# Sheet1.net
KiCad netlist of a schematic drawn in Altium Designer
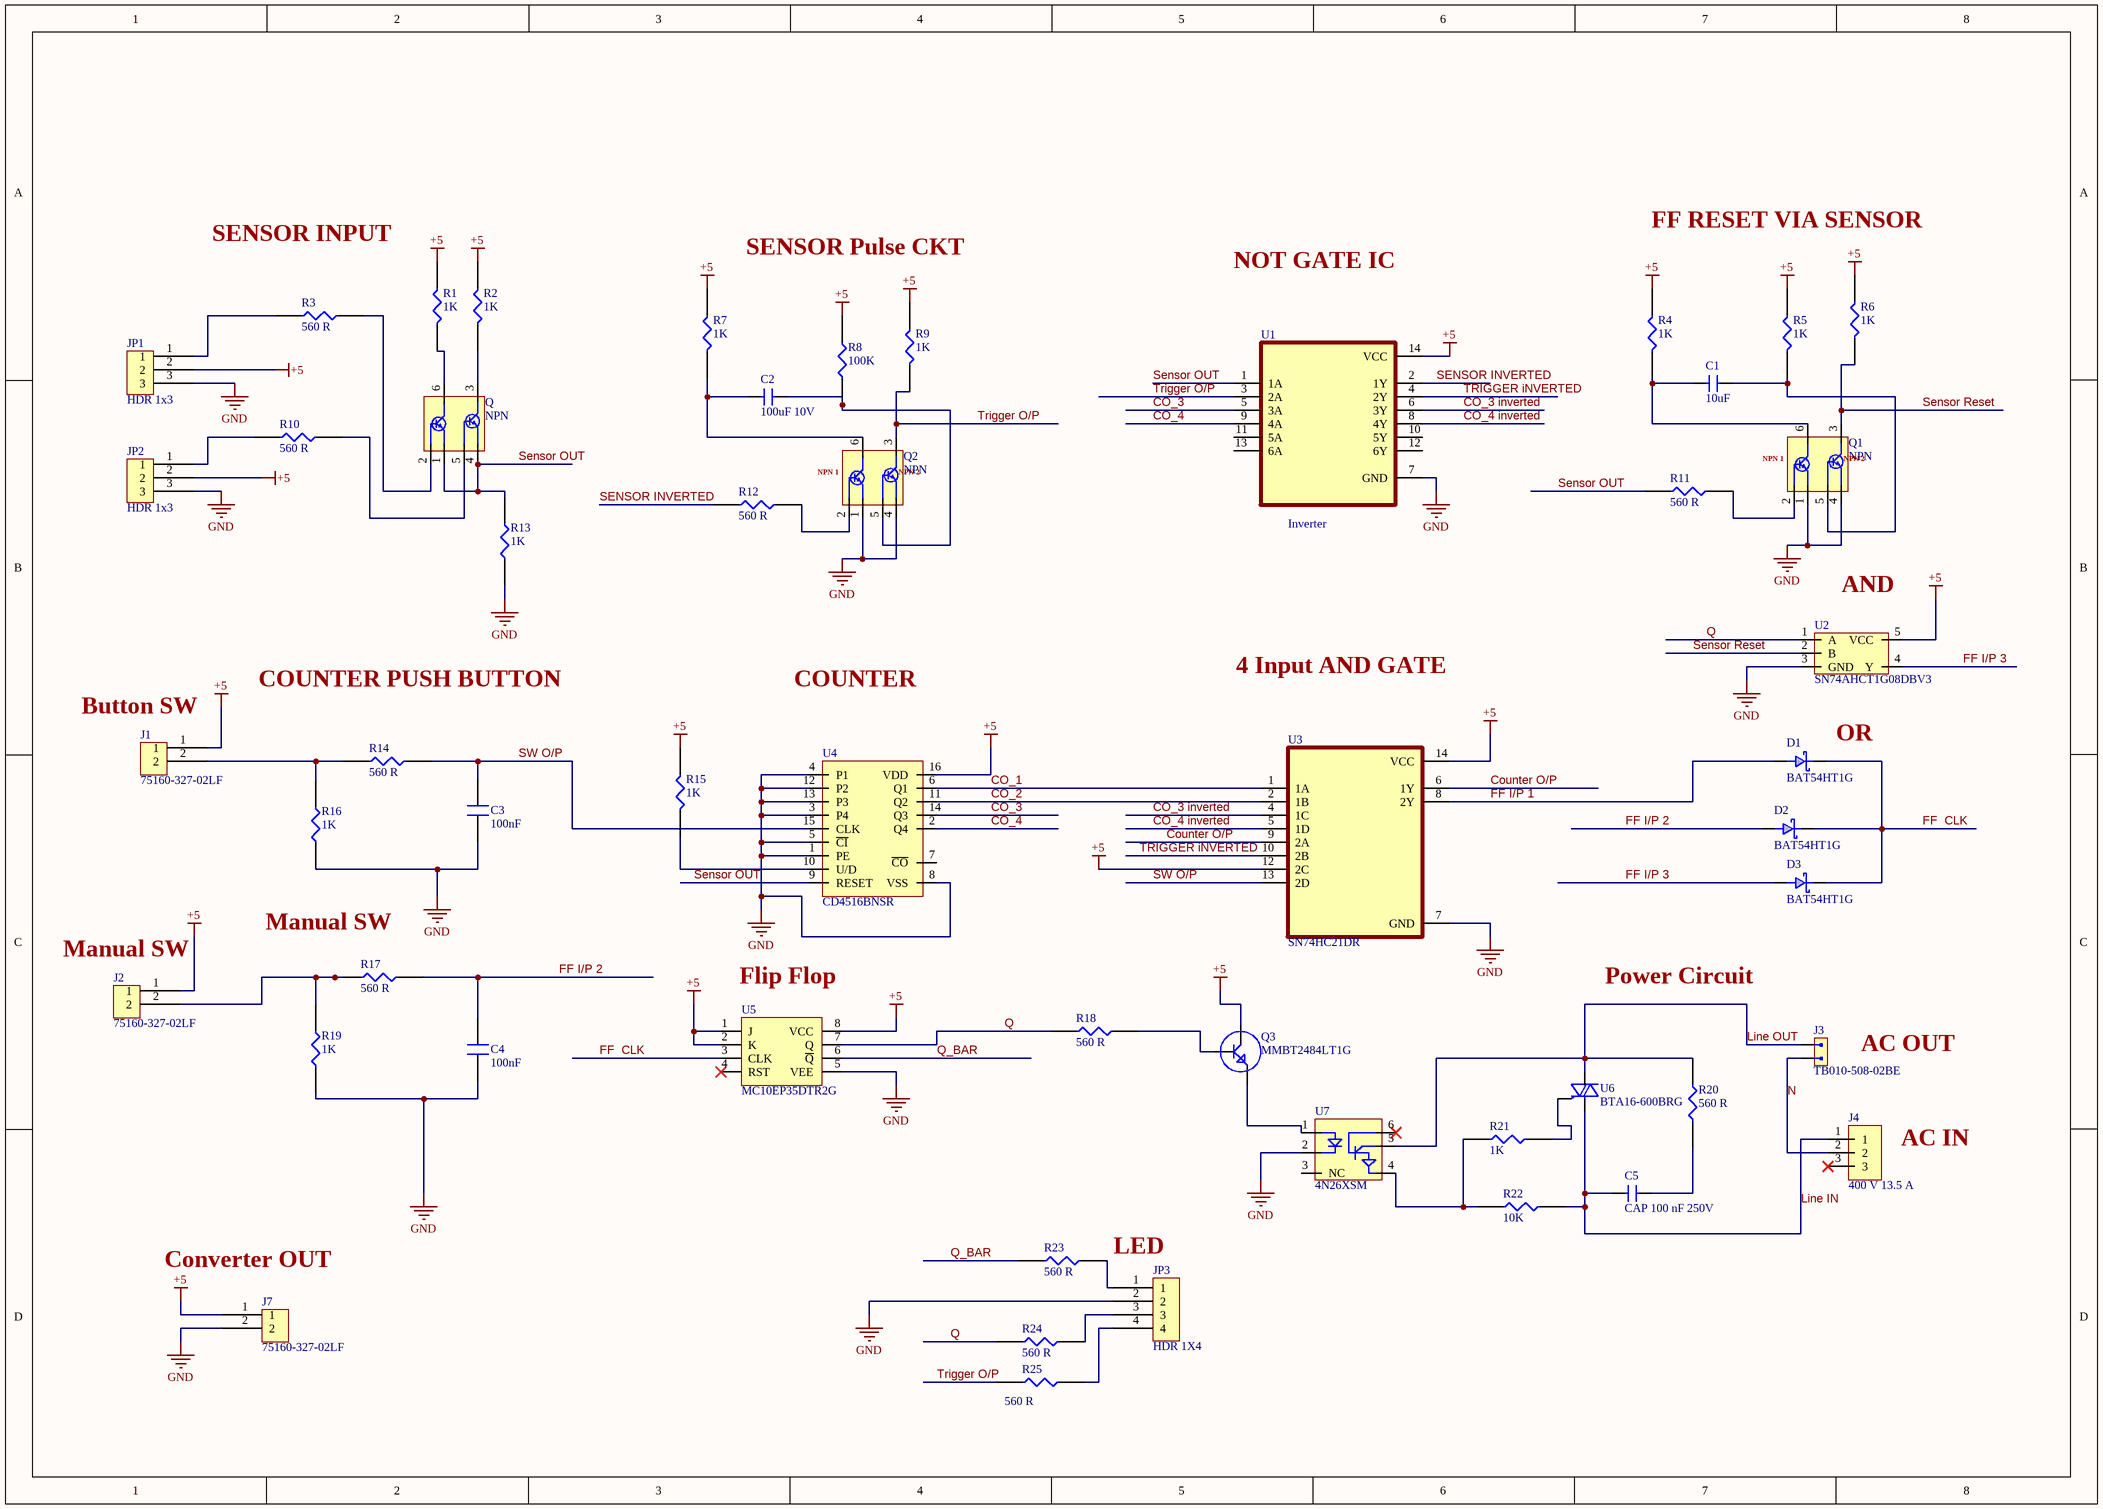
[diagram p0: Sheet1.SchDoc]

(export (version "E")
  (design (tool "Eeschema 10.0.6"))
  (components
    (comp (ref "C1")
      (value "10uF")
      (footprint "CAP_0805")
      (fields
        (field (name "MANUFACTURER") "TDK")
        (field (name "MANUFACTURER PART NUMBER") "C2012X5R1C106M125AC")
        (field (name "TOLERANCE") "20%")
      )
      (libsource (lib "Component Schematic Library V1") (part "CAP_10uF_0805"))
    )
    (comp (ref "C2")
      (value "100uF 10V")
      (footprint "CAP3216")
      (description "C Series 1206 100 uF 10 V ±20 % Tolerance JB SMT Multilayer Ceramic Capacitor")
      (fields
        (field (name "MANUFACTURER") "TDK")
        (field (name "MANUFACTURER PART NUMBER") "C3216JB1A107M160AC")
      )
      (libsource (lib "Component Schematic Library V1") (part "CAP 100 uF SMD Non Polar"))
    )
    (comp (ref "C3")
      (value "100nF")
      (footprint "CAP_0805")
      (description "C Series 0805 0.1 uF 50 V ±10 % Tolerance X7R SMT Multilayer Ceramic Capacitor")
      (fields
        (field (name "MANUFACTURER") "TDK")
        (field (name "MANUFACTURER PART NUMBER") "C2012X7R1H104K085AA")
      )
      (libsource (lib "Component Schematic Library V1") (part "CAP_100nF_0805"))
    )
    (comp (ref "C4")
      (value "100nF")
      (footprint "CAP_0805")
      (description "C Series 0805 0.1 uF 50 V ±10 % Tolerance X7R SMT Multilayer Ceramic Capacitor")
      (fields
        (field (name "MANUFACTURER") "TDK")
        (field (name "MANUFACTURER PART NUMBER") "C2012X7R1H104K085AA")
      )
      (libsource (lib "Component Schematic Library V1") (part "CAP_100nF_0805"))
    )
    (comp (ref "C5")
      (value "CAP 100 nF 250V")
      (footprint "CAP_0805")
      (description "C Series 0805 0.1 uF 250 V ±20 % Tolerance X7T SMT Multilayer Ceramic Capacitor")
      (libsource (lib "Component Schematic Library V1") (part "CAP 100 nF 250V"))
    )
    (comp (ref "D1")
      (value "BAT54HT1G")
      (footprint "SOD323")
      (description "VR=30V IF=200mA 10pF P=200mW")
      (fields (field (name "MANUFACTURER") "ON Semiconductor / Fairchild"))
      (libsource (lib "Component Schematic Library V1") (part "Shottky_Diode"))
    )
    (comp (ref "D2")
      (value "BAT54HT1G")
      (footprint "SOD323")
      (description "VR=30V IF=200mA 10pF P=200mW")
      (fields (field (name "MANUFACTURER") "ON Semiconductor / Fairchild"))
      (libsource (lib "Component Schematic Library V1") (part "Shottky_Diode"))
    )
    (comp (ref "D3")
      (value "BAT54HT1G")
      (footprint "SOD323")
      (description "VR=30V IF=200mA 10pF P=200mW")
      (fields (field (name "MANUFACTURER") "ON Semiconductor / Fairchild"))
      (libsource (lib "Component Schematic Library V1") (part "Shottky_Diode"))
    )
    (comp (ref "J1")
      (value "75160-327-02LF")
      (footprint "HDR 1x2")
      (description "Conn Unshrouded Header HDR 2 POS 2.54mm Solder ST Thru-Hole Poly Bag")
      (fields (field (name "MANUFACTURER") "Amphenol ICC / FCI"))
      (libsource (lib "") (part "MALE_HDR_1X2_1"))
    )
    (comp (ref "J2")
      (value "75160-327-02LF")
      (footprint "HDR 1x2")
      (description "Conn Unshrouded Header HDR 2 POS 2.54mm Solder ST Thru-Hole Poly Bag")
      (fields (field (name "MANUFACTURER") "Amphenol ICC / FCI"))
      (libsource (lib "") (part "MALE_HDR_1X2_1"))
    )
    (comp (ref "J3")
      (value "TB010-508-02BE")
      (footprint "CUI_TB010-508-02BE")
      (description "2~24 Poles, Screw Type, Horizontal, 5.08 Pitch, 26~12 (AWG), Terminal Block Connector")
      (fields (field (name "MANUFACTURER") "CUI Devices"))
      (libsource (lib "Component Schematic Library V1") (part "Screw terminal 2 pin"))
    )
    (comp (ref "J4")
      (value "400 V 13.5 A")
      (footprint "Screw 5mm 3 Terminal")
      (description "Phoenix Contact 5441540, BC-500X10- 3 BK PCB terminal blo")
      (fields
        (field (name "MANUFACTURER") "Phoenix Contact")
        (field (name "MANUFACTURER PART NUMBER") "5441540")
      )
      (libsource (lib "Component Schematic Library V1") (part "Screw Terminal HV 3 pins"))
    )
    (comp (ref "J7")
      (value "75160-327-02LF")
      (footprint "HDR 1x2")
      (description "Conn Unshrouded Header HDR 2 POS 2.54mm Solder ST Thru-Hole Poly Bag")
      (fields (field (name "MANUFACTURER") "Amphenol ICC / FCI"))
      (libsource (lib "Component Schematic Library V1") (part "MALE_HDR_1X2"))
    )
    (comp (ref "JP1")
      (value "HDR 1x3")
      (footprint "HDR 1x3")
      (description "Conn Unshrouded Header HDR 3 POS 2.54mm Solder ST Top Entry Thru-Hole BergStik® Bulk")
      (fields
        (field (name "MANUFACTURER") "Amphenol ICC / FCI")
        (field (name "MANUFACTURER PART NUMBER") "68797-403HLF")
      )
      (libsource (lib "Component Schematic Library V1") (part "Male_HDR_1X3_Unschrouded"))
    )
    (comp (ref "JP2")
      (value "HDR 1x3")
      (footprint "HDR 1x3")
      (description "Conn Unshrouded Header HDR 3 POS 2.54mm Solder ST Top Entry Thru-Hole BergStik® Bulk")
      (fields
        (field (name "MANUFACTURER") "Amphenol ICC / FCI")
        (field (name "MANUFACTURER PART NUMBER") "68797-403HLF")
      )
      (libsource (lib "Component Schematic Library V1") (part "Male_HDR_1X3_Unschrouded"))
    )
    (comp (ref "JP3")
      (value "HDR 1X4")
      (footprint "HDR 1X4")
      (description "Conn Unshrouded Header HDR 4 POS 2.54mm Solder ST Thru-Hole Bag")
      (fields
        (field (name "MANUFACTURER") "Amphenol ICC")
        (field (name "MANUFACTURER PART NUMBER") "68001-204HLF")
      )
      (libsource (lib "Component Schematic Library V1") (part "MALE_HDR_4X1_Unschrouded"))
    )
    (comp (ref "Q")
      (value "NPN")
      (footprint "SOT-363")
      (description "三极管 2NPN Vceo=40V Ic=200mA Pd=225mW")
      (fields
        (field (name "MANUFACTURER") "Pan Jit")
        (field (name "MANUFACTURER PART NUMBER") "MMDT3904_R1_00001")
      )
      (libsource (lib "Component Schematic Library V1") (part "NPN SMD 2 CKT"))
    )
    (comp (ref "Q1")
      (value "NPN")
      (footprint "SOT-363")
      (description "三极管 2NPN Vceo=40V Ic=200mA Pd=225mW")
      (fields
        (field (name "MANUFACTURER") "Pan Jit")
        (field (name "MANUFACTURER PART NUMBER") "MMDT3904_R1_00001")
      )
      (libsource (lib "Component Schematic Library V1") (part "NPN SMD 2 CKT"))
    )
    (comp (ref "Q2")
      (value "NPN")
      (footprint "SOT-363")
      (description "三极管 2NPN Vceo=40V Ic=200mA Pd=225mW")
      (fields
        (field (name "MANUFACTURER") "Pan Jit")
        (field (name "MANUFACTURER PART NUMBER") "MMDT3904_R1_00001")
      )
      (libsource (lib "Component Schematic Library V1") (part "NPN SMD 2 CKT"))
    )
    (comp (ref "Q3")
      (value "MMBT2484LT1G")
      (footprint "SOT23-3")
      (description "Transistor Bipolar (BJT) NPN 60V 100mA 225mW Surface Mount SOT-23-3")
      (fields (field (name "MANUFACTURER") "ON Semiconductor"))
      (libsource (lib "Component Schematic Library V1") (part "BJT SMD"))
    )
    (comp (ref "R1")
      (value "1K")
      (footprint "R_0805")
      (description "贴片电阻 1000Ω ± 1.00% 0.125W ± 100ppm/℃ 0805")
      (fields
        (field (name "MANUFACTURER") "Yageo")
        (field (name "MANUFACTURER PART NUMBER") "RC0805FR-071KL")
      )
      (libsource (lib "Component Schematic Library V1") (part "RES_1_K_0805"))
    )
    (comp (ref "R2")
      (value "1K")
      (footprint "R_0805")
      (description "贴片电阻 1000Ω ± 1.00% 0.125W ± 100ppm/℃ 0805")
      (fields
        (field (name "MANUFACTURER") "Yageo")
        (field (name "MANUFACTURER PART NUMBER") "RC0805FR-071KL")
      )
      (libsource (lib "Component Schematic Library V1") (part "RES_1_K_0805"))
    )
    (comp (ref "R3")
      (value "560 R")
      (footprint "R_0805")
      (description "贴片电阻 560Ω ± 1.00% 0.125W ± 100ppm/℃ 0805")
      (fields
        (field (name "MANUFACTURER") "Yageo")
        (field (name "MANUFACTURER PART NUMBER") "RC0805FR-07560RL")
      )
      (libsource (lib "Component Schematic Library V1") (part "RES_560_Ohm_0805"))
    )
    (comp (ref "R4")
      (value "1K")
      (footprint "R_0805")
      (description "贴片电阻 1000Ω ± 1.00% 0.125W ± 100ppm/℃ 0805")
      (fields
        (field (name "MANUFACTURER") "Yageo")
        (field (name "MANUFACTURER PART NUMBER") "RC0805FR-071KL")
      )
      (libsource (lib "Component Schematic Library V1") (part "RES_1_K_0805"))
    )
    (comp (ref "R5")
      (value "1K")
      (footprint "R_0805")
      (description "贴片电阻 1000Ω ± 1.00% 0.125W ± 100ppm/℃ 0805")
      (fields
        (field (name "MANUFACTURER") "Yageo")
        (field (name "MANUFACTURER PART NUMBER") "RC0805FR-071KL")
      )
      (libsource (lib "Component Schematic Library V1") (part "RES_1_K_0805"))
    )
    (comp (ref "R6")
      (value "1K")
      (footprint "R_0805")
      (description "贴片电阻 1000Ω ± 1.00% 0.125W ± 100ppm/℃ 0805")
      (fields
        (field (name "MANUFACTURER") "Yageo")
        (field (name "MANUFACTURER PART NUMBER") "RC0805FR-071KL")
      )
      (libsource (lib "Component Schematic Library V1") (part "RES_1_K_0805"))
    )
    (comp (ref "R7")
      (value "1K")
      (footprint "R_0805")
      (description "贴片电阻 1000Ω ± 1.00% 0.125W ± 100ppm/℃ 0805")
      (fields
        (field (name "MANUFACTURER") "Yageo")
        (field (name "MANUFACTURER PART NUMBER") "RC0805FR-071KL")
      )
      (libsource (lib "Component Schematic Library V1") (part "RES_1_K_0805"))
    )
    (comp (ref "R8")
      (value "100K")
      (footprint "R_0805")
      (description "贴片电阻 100000Ω ± 1.00% 0.125W ± 100ppm/℃ 0805")
      (fields
        (field (name "MANUFACTURER") "Yageo")
        (field (name "MANUFACTURER PART NUMBER") "RC0805FR-07100KL")
      )
      (libsource (lib "Component Schematic Library V1") (part "RES_100_K_0805"))
    )
    (comp (ref "R9")
      (value "1K")
      (footprint "R_0805")
      (description "贴片电阻 1000Ω ± 1.00% 0.125W ± 100ppm/℃ 0805")
      (fields
        (field (name "MANUFACTURER") "Yageo")
        (field (name "MANUFACTURER PART NUMBER") "RC0805FR-071KL")
      )
      (libsource (lib "Component Schematic Library V1") (part "RES_1_K_0805"))
    )
    (comp (ref "R10")
      (value "560 R")
      (footprint "R_0805")
      (description "贴片电阻 560Ω ± 1.00% 0.125W ± 100ppm/℃ 0805")
      (fields
        (field (name "MANUFACTURER") "Yageo")
        (field (name "MANUFACTURER PART NUMBER") "RC0805FR-07560RL")
      )
      (libsource (lib "Component Schematic Library V1") (part "RES_560_Ohm_0805"))
    )
    (comp (ref "R11")
      (value "560 R")
      (footprint "R_0805")
      (description "贴片电阻 560Ω ± 1.00% 0.125W ± 100ppm/℃ 0805")
      (fields
        (field (name "MANUFACTURER") "Yageo")
        (field (name "MANUFACTURER PART NUMBER") "RC0805FR-07560RL")
      )
      (libsource (lib "Component Schematic Library V1") (part "RES_560_Ohm_0805"))
    )
    (comp (ref "R12")
      (value "560 R")
      (footprint "R_0805")
      (description "贴片电阻 560Ω ± 1.00% 0.125W ± 100ppm/℃ 0805")
      (fields
        (field (name "MANUFACTURER") "Yageo")
        (field (name "MANUFACTURER PART NUMBER") "RC0805FR-07560RL")
      )
      (libsource (lib "Component Schematic Library V1") (part "RES_560_Ohm_0805"))
    )
    (comp (ref "R13")
      (value "1K")
      (footprint "R_0805")
      (description "贴片电阻 1000Ω ± 1.00% 0.125W ± 100ppm/℃ 0805")
      (fields
        (field (name "MANUFACTURER") "Yageo")
        (field (name "MANUFACTURER PART NUMBER") "RC0805FR-071KL")
      )
      (libsource (lib "Component Schematic Library V1") (part "RES_1_K_0805"))
    )
    (comp (ref "R14")
      (value "560 R")
      (footprint "R_0805")
      (description "贴片电阻 560Ω ± 1.00% 0.125W ± 100ppm/℃ 0805")
      (fields
        (field (name "MANUFACTURER") "Yageo")
        (field (name "MANUFACTURER PART NUMBER") "RC0805FR-07560RL")
      )
      (libsource (lib "Component Schematic Library V1") (part "RES_560_Ohm_0805"))
    )
    (comp (ref "R15")
      (value "1K")
      (footprint "R_0805")
      (description "贴片电阻 1000Ω ± 1.00% 0.125W ± 100ppm/℃ 0805")
      (fields
        (field (name "MANUFACTURER") "Yageo")
        (field (name "MANUFACTURER PART NUMBER") "RC0805FR-071KL")
      )
      (libsource (lib "Component Schematic Library V1") (part "RES_1_K_0805"))
    )
    (comp (ref "R16")
      (value "1K")
      (footprint "R_0805")
      (description "贴片电阻 1000Ω ± 1.00% 0.125W ± 100ppm/℃ 0805")
      (fields
        (field (name "MANUFACTURER") "Yageo")
        (field (name "MANUFACTURER PART NUMBER") "RC0805FR-071KL")
      )
      (libsource (lib "Component Schematic Library V1") (part "RES_1_K_0805"))
    )
    (comp (ref "R17")
      (value "560 R")
      (footprint "R_0805")
      (description "贴片电阻 560Ω ± 1.00% 0.125W ± 100ppm/℃ 0805")
      (fields
        (field (name "MANUFACTURER") "Yageo")
        (field (name "MANUFACTURER PART NUMBER") "RC0805FR-07560RL")
      )
      (libsource (lib "Component Schematic Library V1") (part "RES_560_Ohm_0805"))
    )
    (comp (ref "R18")
      (value "560 R")
      (footprint "R_0805")
      (description "贴片电阻 560Ω ± 1.00% 0.125W ± 100ppm/℃ 0805")
      (fields
        (field (name "MANUFACTURER") "Yageo")
        (field (name "MANUFACTURER PART NUMBER") "RC0805FR-07560RL")
      )
      (libsource (lib "Component Schematic Library V1") (part "RES_560_Ohm_0805"))
    )
    (comp (ref "R19")
      (value "1K")
      (footprint "R_0805")
      (description "贴片电阻 1000Ω ± 1.00% 0.125W ± 100ppm/℃ 0805")
      (fields
        (field (name "MANUFACTURER") "Yageo")
        (field (name "MANUFACTURER PART NUMBER") "RC0805FR-071KL")
      )
      (libsource (lib "Component Schematic Library V1") (part "RES_1_K_0805"))
    )
    (comp (ref "R20")
      (value "560 R")
      (footprint "R_0805")
      (description "贴片电阻 560Ω ± 1.00% 0.125W ± 100ppm/℃ 0805")
      (fields
        (field (name "MANUFACTURER") "Yageo")
        (field (name "MANUFACTURER PART NUMBER") "RC0805FR-07560RL")
      )
      (libsource (lib "Component Schematic Library V1") (part "RES_560_Ohm_0805"))
    )
    (comp (ref "R21")
      (value "1K")
      (footprint "R_0805")
      (description "贴片电阻 1000Ω ± 1.00% 0.125W ± 100ppm/℃ 0805")
      (fields
        (field (name "MANUFACTURER") "Yageo")
        (field (name "MANUFACTURER PART NUMBER") "RC0805FR-071KL")
      )
      (libsource (lib "Component Schematic Library V1") (part "RES_1_K_0805"))
    )
    (comp (ref "R22")
      (value "10K")
      (footprint "R_0805")
      (description "贴片电阻 10000Ω ± 1.00% 0.125W ± 100ppm/℃ 0805")
      (fields
        (field (name "MANUFACTURER") "Yageo")
        (field (name "MANUFACTURER PART NUMBER") "RC0805FR-0710KL")
      )
      (libsource (lib "Component Schematic Library V1") (part "RES_10_K_0805"))
    )
    (comp (ref "R23")
      (value "560 R")
      (footprint "R_0805")
      (description "贴片电阻 560Ω ± 1.00% 0.125W ± 100ppm/℃ 0805")
      (fields
        (field (name "MANUFACTURER") "Yageo")
        (field (name "MANUFACTURER PART NUMBER") "RC0805FR-07560RL")
      )
      (libsource (lib "Component Schematic Library V1") (part "RES_560_Ohm_0805"))
    )
    (comp (ref "R24")
      (value "560 R")
      (footprint "R_0805")
      (description "贴片电阻 560Ω ± 1.00% 0.125W ± 100ppm/℃ 0805")
      (fields
        (field (name "MANUFACTURER") "Yageo")
        (field (name "MANUFACTURER PART NUMBER") "RC0805FR-07560RL")
      )
      (libsource (lib "Component Schematic Library V1") (part "RES_560_Ohm_0805"))
    )
    (comp (ref "R25")
      (value "560 R")
      (footprint "R_0805")
      (description "贴片电阻 560Ω ± 1.00% 0.125W ± 100ppm/℃ 0805")
      (fields
        (field (name "MANUFACTURER") "Yageo")
        (field (name "MANUFACTURER PART NUMBER") "RC0805FR-07560RL")
      )
      (libsource (lib "Component Schematic Library V1") (part "RES_560_Ohm_0805"))
    )
    (comp (ref "U1")
      (value "Inverter")
      (footprint "14-TSSOP")
      (description "6-ch, 4.5-V to 5.5-V inverters with Schmitt-Trigger inputs 14-TSSOP -40 to 85")
      (fields
        (field (name "MANUFACTURER") "Texas Instruments")
        (field (name "MANUFACTURER PART NUMBER") "SN74ACT14PWR")
      )
      (libsource (lib "Component Schematic Library V1") (part "NOT GATE 7 Channel"))
    )
    (comp (ref "U2")
      (value "SN74AHCT1G08DBV3")
      (footprint "SOT-23-5")
      (description "Single 2-input, 4.5-V to 5.5-V AND gate with TTL-compatible CMOS inputs 5-SOT-23 -40 to 125")
      (fields (field (name "MANUFACTURER") "Texas Instruments"))
      (libsource (lib "Component Schematic Library V1") (part "AND 2 INP 1 CKT"))
    )
    (comp (ref "U3")
      (value "SN74HC21DR")
      (footprint "SOIC 14")
      (description "AND Gate IC 2 Channel  14-SOIC")
      (fields (field (name "MANUFACTURER") "Texas Instruments"))
      (libsource (lib "Component Schematic Library V1") (part "AND 4 inp 2 ch SMD"))
    )
    (comp (ref "U4")
      (value "CD4516BNSR")
      (footprint "SOIC 16")
      (description "CMOS Presettable Binary Up/Down Counter 16-SO -55 to 125")
      (fields (field (name "MANUFACTURER") "Texas Instruments"))
      (libsource (lib "Component Schematic Library V1") (part "COUNTER CD4516BNSR"))
    )
    (comp (ref "U5")
      (value "MC10EP35DTR2G")
      (footprint "8-TSSOP")
      (description "Flip Flop JK-Type Pos-Edge 1-Element 8-Pin TSSOP T/R")
      (fields (field (name "MANUFACTURER") "ON Semiconductor"))
      (libsource (lib "Component Schematic Library V1") (part "JK Flipflop"))
    )
    (comp (ref "U6")
      (value "BTA16-600BRG")
      (footprint "BAT16")
      (description "TRIAC Standard 600V 16A Through Hole TO-220AB")
      (libsource (lib "Component Schematic Library V1") (part "Triac"))
    )
    (comp (ref "U7")
      (value "4N26XSM")
      (footprint "SMD 6")
      (description "DC-IN 1-CH Transistor With Base DC-OUT 6-Pin PDIP SMD")
      (fields (field (name "MANUFACTURER") "Isocom"))
      (libsource (lib "Component Schematic Library V1") (part "4N26XSM"))
    )
  )
  (nets
    (net (code "1") (name "+5") (class "Default")
      (node (ref "J1") (pin "1") (pinfunction "1_1") (pintype "passive"))
      (node (ref "J2") (pin "1") (pinfunction "1_1") (pintype "passive"))
      (node (ref "J7") (pin "1") (pinfunction "1_1") (pintype "passive"))
      (node (ref "JP1") (pin "2") (pinfunction "2_2") (pintype "passive"))
      (node (ref "JP2") (pin "2") (pinfunction "2_2") (pintype "passive"))
      (node (ref "Q3") (pin "3") (pinfunction "3_3") (pintype "passive"))
      (node (ref "R1") (pin "2") (pinfunction "3_2") (pintype "passive"))
      (node (ref "R15") (pin "2") (pinfunction "3_2") (pintype "passive"))
      (node (ref "R2") (pin "2") (pinfunction "3_2") (pintype "passive"))
      (node (ref "R4") (pin "2") (pinfunction "3_2") (pintype "passive"))
      (node (ref "R5") (pin "2") (pinfunction "3_2") (pintype "passive"))
      (node (ref "R6") (pin "2") (pinfunction "3_2") (pintype "passive"))
      (node (ref "R7") (pin "2") (pinfunction "3_2") (pintype "passive"))
      (node (ref "R8") (pin "2") (pinfunction "3_2") (pintype "passive"))
      (node (ref "R9") (pin "2") (pinfunction "3_2") (pintype "passive"))
      (node (ref "U1") (pin "14") (pinfunction "VCC_14") (pintype "passive"))
      (node (ref "U2") (pin "5") (pinfunction "VCC_5") (pintype "passive"))
      (node (ref "U3") (pin "12") (pinfunction "2C_12") (pintype "passive"))
      (node (ref "U3") (pin "14") (pinfunction "VCC_14") (pintype "passive"))
      (node (ref "U4") (pin "16") (pinfunction "VDD_16") (pintype "passive"))
      (node (ref "U5") (pin "1") (pinfunction "J_1") (pintype "passive"))
      (node (ref "U5") (pin "2") (pinfunction "K_2") (pintype "passive"))
      (node (ref "U5") (pin "8") (pinfunction "VCC_8") (pintype "passive"))
    )
    (net (code "2") (name "/CO_1") (class "Default")
      (node (ref "U3") (pin "1") (pinfunction "1A_1") (pintype "passive"))
      (node (ref "U4") (pin "6") (pinfunction "Q1_6") (pintype "passive"))
    )
    (net (code "3") (name "/CO_2") (class "Default")
      (node (ref "U3") (pin "2") (pinfunction "1B_2") (pintype "passive"))
      (node (ref "U4") (pin "11") (pinfunction "Q2_11") (pintype "passive"))
    )
    (net (code "4") (name "/CO_3") (class "Default")
      (node (ref "U1") (pin "5") (pinfunction "3A_5") (pintype "passive"))
      (node (ref "U4") (pin "14") (pinfunction "Q3_14") (pintype "passive"))
    )
    (net (code "5") (name "/CO_3 inverted") (class "Default")
      (node (ref "U1") (pin "6") (pinfunction "3Y_6") (pintype "passive"))
      (node (ref "U3") (pin "4") (pinfunction "1C_4") (pintype "passive"))
    )
    (net (code "6") (name "/CO_4") (class "Default")
      (node (ref "U1") (pin "9") (pinfunction "4A_9") (pintype "passive"))
      (node (ref "U4") (pin "2") (pinfunction "Q4_2") (pintype "passive"))
    )
    (net (code "7") (name "/CO_4 inverted") (class "Default")
      (node (ref "U1") (pin "8") (pinfunction "4Y_8") (pintype "passive"))
      (node (ref "U3") (pin "5") (pinfunction "1D_5") (pintype "passive"))
    )
    (net (code "8") (name "/Counter O{slash}P") (class "Default")
      (node (ref "U3") (pin "6") (pinfunction "1Y_6") (pintype "passive"))
      (node (ref "U3") (pin "9") (pinfunction "2A_9") (pintype "passive"))
    )
    (net (code "9") (name "/FF  CLK") (class "Default")
      (node (ref "D1") (pin "1") (pinfunction "Cathode_1") (pintype "passive"))
      (node (ref "D2") (pin "1") (pinfunction "Cathode_1") (pintype "passive"))
      (node (ref "D3") (pin "1") (pinfunction "Cathode_1") (pintype "passive"))
      (node (ref "U5") (pin "3") (pinfunction "CLK_3") (pintype "passive"))
    )
    (net (code "10") (name "/FF I{slash}P 1") (class "Default")
      (node (ref "D1") (pin "2") (pinfunction "Anode_2") (pintype "passive"))
      (node (ref "U3") (pin "8") (pinfunction "2Y_8") (pintype "passive"))
    )
    (net (code "11") (name "/FF I{slash}P 2") (class "Default")
      (node (ref "C4") (pin "1") (pinfunction "1_1") (pintype "passive"))
      (node (ref "D2") (pin "2") (pinfunction "Anode_2") (pintype "passive"))
      (node (ref "R17") (pin "2") (pinfunction "3_2") (pintype "passive"))
    )
    (net (code "12") (name "/FF I{slash}P 3") (class "Default")
      (node (ref "D3") (pin "2") (pinfunction "Anode_2") (pintype "passive"))
      (node (ref "U2") (pin "4") (pinfunction "Y_4") (pintype "passive"))
    )
    (net (code "13") (name "/Line IN") (class "Default")
      (node (ref "C5") (pin "1") (pinfunction "1_1") (pintype "passive"))
      (node (ref "J4") (pin "1") (pinfunction "1_1") (pintype "passive"))
      (node (ref "R22") (pin "2") (pinfunction "3_2") (pintype "passive"))
      (node (ref "U6") (pin "1") (pinfunction "A1_1") (pintype "passive"))
    )
    (net (code "14") (name "/Line OUT") (class "Default")
      (node (ref "J3") (pin "1") (pinfunction "1_1") (pintype "passive"))
      (node (ref "R20") (pin "2") (pinfunction "3_2") (pintype "passive"))
      (node (ref "U6") (pin "2") (pinfunction "A2_2") (pintype "passive"))
      (node (ref "U7") (pin "5") (pinfunction "5_5") (pintype "passive"))
    )
    (net (code "15") (name "/N") (class "Default")
      (node (ref "J3") (pin "2") (pinfunction "2_2") (pintype "passive"))
      (node (ref "J4") (pin "2") (pinfunction "2_2") (pintype "passive"))
    )
    (net (code "16") (name "/Q") (class "Default")
      (node (ref "R18") (pin "1") (pinfunction "2_1") (pintype "passive"))
      (node (ref "R24") (pin "1") (pinfunction "2_1") (pintype "passive"))
      (node (ref "U2") (pin "1") (pinfunction "A_1") (pintype "passive"))
      (node (ref "U5") (pin "7") (pinfunction "Q_7") (pintype "passive"))
    )
    (net (code "17") (name "/Q_BAR") (class "Default")
      (node (ref "R23") (pin "1") (pinfunction "2_1") (pintype "passive"))
      (node (ref "U5") (pin "6") (pinfunction "~{Q}_6") (pintype "passive"))
    )
    (net (code "18") (name "/SENSOR INVERTED") (class "Default")
      (node (ref "R12") (pin "1") (pinfunction "2_1") (pintype "passive"))
      (node (ref "U1") (pin "2") (pinfunction "1Y_2") (pintype "passive"))
    )
    (net (code "19") (name "/SW O{slash}P") (class "Default")
      (node (ref "C3") (pin "1") (pinfunction "1_1") (pintype "passive"))
      (node (ref "R14") (pin "2") (pinfunction "3_2") (pintype "passive"))
      (node (ref "U3") (pin "13") (pinfunction "2D_13") (pintype "passive"))
      (node (ref "U4") (pin "15") (pinfunction "CLK_15") (pintype "passive"))
    )
    (net (code "20") (name "/Sensor OUT") (class "Default")
      (node (ref "Q") (pin "1") (pinfunction "E1_1") (pintype "passive"))
      (node (ref "Q") (pin "4") (pinfunction "E2_4") (pintype "passive"))
      (node (ref "R11") (pin "1") (pinfunction "2_1") (pintype "passive"))
      (node (ref "R13") (pin "2") (pinfunction "3_2") (pintype "passive"))
      (node (ref "U1") (pin "1") (pinfunction "1A_1") (pintype "passive"))
      (node (ref "U4") (pin "9") (pinfunction "RESET_9") (pintype "passive"))
    )
    (net (code "21") (name "/Sensor Reset") (class "Default")
      (node (ref "Q1") (pin "3") (pinfunction "C2_3") (pintype "passive"))
      (node (ref "R6") (pin "1") (pinfunction "2_1") (pintype "passive"))
      (node (ref "U2") (pin "2") (pinfunction "B_2") (pintype "passive"))
    )
    (net (code "22") (name "/TRIGGER iNVERTED") (class "Default")
      (node (ref "U1") (pin "4") (pinfunction "2Y_4") (pintype "passive"))
      (node (ref "U3") (pin "10") (pinfunction "2B_10") (pintype "passive"))
    )
    (net (code "23") (name "/Trigger O{slash}P") (class "Default")
      (node (ref "Q2") (pin "3") (pinfunction "C2_3") (pintype "passive"))
      (node (ref "R25") (pin "1") (pinfunction "2_1") (pintype "passive"))
      (node (ref "R9") (pin "1") (pinfunction "2_1") (pintype "passive"))
      (node (ref "U1") (pin "3") (pinfunction "2A_3") (pintype "passive"))
    )
    (net (code "24") (name "GND") (class "Default")
      (node (ref "C3") (pin "2") (pinfunction "2_2") (pintype "passive"))
      (node (ref "C4") (pin "2") (pinfunction "2_2") (pintype "passive"))
      (node (ref "J7") (pin "2") (pinfunction "2_2") (pintype "passive"))
      (node (ref "JP1") (pin "3") (pinfunction "3_3") (pintype "passive"))
      (node (ref "JP2") (pin "3") (pinfunction "3_3") (pintype "passive"))
      (node (ref "JP3") (pin "2") (pinfunction "2_2") (pintype "passive"))
      (node (ref "Q1") (pin "1") (pinfunction "E1_1") (pintype "passive"))
      (node (ref "Q1") (pin "4") (pinfunction "E2_4") (pintype "passive"))
      (node (ref "Q2") (pin "1") (pinfunction "E1_1") (pintype "passive"))
      (node (ref "Q2") (pin "4") (pinfunction "E2_4") (pintype "passive"))
      (node (ref "R13") (pin "1") (pinfunction "2_1") (pintype "passive"))
      (node (ref "R16") (pin "2") (pinfunction "3_2") (pintype "passive"))
      (node (ref "R19") (pin "2") (pinfunction "3_2") (pintype "passive"))
      (node (ref "U1") (pin "7") (pinfunction "GND_7") (pintype "passive"))
      (node (ref "U2") (pin "3") (pinfunction "GND_3") (pintype "passive"))
      (node (ref "U3") (pin "7") (pinfunction "GND_7") (pintype "passive"))
      (node (ref "U4") (pin "1") (pinfunction "PE_1") (pintype "passive"))
      (node (ref "U4") (pin "12") (pinfunction "P2_12") (pintype "passive"))
      (node (ref "U4") (pin "13") (pinfunction "P3_13") (pintype "passive"))
      (node (ref "U4") (pin "3") (pinfunction "P4_3") (pintype "passive"))
      (node (ref "U4") (pin "4") (pinfunction "P1_4") (pintype "passive"))
      (node (ref "U4") (pin "5") (pinfunction "~{CI}_5") (pintype "passive"))
      (node (ref "U4") (pin "8") (pinfunction "VSS_8") (pintype "passive"))
      (node (ref "U5") (pin "5") (pinfunction "VEE_5") (pintype "passive"))
      (node (ref "U7") (pin "2") (pinfunction "2_2") (pintype "passive"))
    )
    (net (code "25") (name "Net-(Q-B1)") (class "Default")
      (node (ref "Q") (pin "2") (pinfunction "B1_2") (pintype "passive"))
      (node (ref "R3") (pin "2") (pinfunction "3_2") (pintype "passive"))
    )
    (net (code "26") (name "Net-(Q-B2)") (class "Default")
      (node (ref "Q") (pin "5") (pinfunction "B2_5") (pintype "passive"))
      (node (ref "R10") (pin "2") (pinfunction "3_2") (pintype "passive"))
    )
    (net (code "27") (name "Net-(Q-C1)") (class "Default")
      (node (ref "Q") (pin "6") (pinfunction "C1_6") (pintype "passive"))
      (node (ref "R1") (pin "1") (pinfunction "2_1") (pintype "passive"))
    )
    (net (code "28") (name "Net-(Q-C2)") (class "Default")
      (node (ref "Q") (pin "3") (pinfunction "C2_3") (pintype "passive"))
      (node (ref "R2") (pin "1") (pinfunction "2_1") (pintype "passive"))
    )
    (net (code "29") (name "Net-(Q1-B1)") (class "Default")
      (node (ref "Q1") (pin "2") (pinfunction "B1_2") (pintype "passive"))
      (node (ref "R11") (pin "2") (pinfunction "3_2") (pintype "passive"))
    )
    (net (code "30") (name "Net-(Q1-B2)") (class "Default")
      (node (ref "C1") (pin "2") (pinfunction "2_2") (pintype "passive"))
      (node (ref "Q1") (pin "5") (pinfunction "B2_5") (pintype "passive"))
      (node (ref "R5") (pin "1") (pinfunction "2_1") (pintype "passive"))
    )
    (net (code "31") (name "Net-(Q1-C1)") (class "Default")
      (node (ref "C1") (pin "1") (pinfunction "1_1") (pintype "passive"))
      (node (ref "Q1") (pin "6") (pinfunction "C1_6") (pintype "passive"))
      (node (ref "R4") (pin "1") (pinfunction "2_1") (pintype "passive"))
    )
    (net (code "32") (name "Net-(Q2-B1)") (class "Default")
      (node (ref "Q2") (pin "2") (pinfunction "B1_2") (pintype "passive"))
      (node (ref "R12") (pin "2") (pinfunction "3_2") (pintype "passive"))
    )
    (net (code "33") (name "Net-(Q2-B2)") (class "Default")
      (node (ref "C2") (pin "2") (pinfunction "2_2") (pintype "passive"))
      (node (ref "Q2") (pin "5") (pinfunction "B2_5") (pintype "passive"))
      (node (ref "R8") (pin "1") (pinfunction "2_1") (pintype "passive"))
    )
    (net (code "34") (name "Net-(Q2-C1)") (class "Default")
      (node (ref "C2") (pin "1") (pinfunction "1_1") (pintype "passive"))
      (node (ref "Q2") (pin "6") (pinfunction "C1_6") (pintype "passive"))
      (node (ref "R7") (pin "1") (pinfunction "2_1") (pintype "passive"))
    )
    (net (code "35") (name "Net-(Q3-Pad2)") (class "Default")
      (node (ref "Q3") (pin "2") (pinfunction "2_2") (pintype "passive"))
      (node (ref "U7") (pin "1") (pinfunction "1_1") (pintype "passive"))
    )
    (net (code "36") (name "Net-(R3-2)") (class "Default")
      (node (ref "JP1") (pin "1") (pinfunction "1_1") (pintype "passive"))
      (node (ref "R3") (pin "1") (pinfunction "2_1") (pintype "passive"))
    )
    (net (code "37") (name "Net-(R10-2)") (class "Default")
      (node (ref "JP2") (pin "1") (pinfunction "1_1") (pintype "passive"))
      (node (ref "R10") (pin "1") (pinfunction "2_1") (pintype "passive"))
    )
    (net (code "38") (name "Net-(R14-2)") (class "Default")
      (node (ref "J1") (pin "2") (pinfunction "2_2") (pintype "passive"))
      (node (ref "R14") (pin "1") (pinfunction "2_1") (pintype "passive"))
      (node (ref "R16") (pin "1") (pinfunction "2_1") (pintype "passive"))
    )
    (net (code "39") (name "Net-(R15-2)") (class "Default")
      (node (ref "R15") (pin "1") (pinfunction "2_1") (pintype "passive"))
      (node (ref "U4") (pin "10") (pinfunction "U/D_10") (pintype "passive"))
    )
    (net (code "40") (name "Net-(R17-2)") (class "Default")
      (node (ref "J2") (pin "2") (pinfunction "2_2") (pintype "passive"))
      (node (ref "R17") (pin "1") (pinfunction "2_1") (pintype "passive"))
      (node (ref "R19") (pin "1") (pinfunction "2_1") (pintype "passive"))
    )
    (net (code "41") (name "Net-(R18-3)") (class "Default")
      (node (ref "Q3") (pin "1") (pinfunction "1_1") (pintype "passive"))
      (node (ref "R18") (pin "2") (pinfunction "3_2") (pintype "passive"))
    )
    (net (code "42") (name "Net-(R20-2)") (class "Default")
      (node (ref "C5") (pin "2") (pinfunction "2_2") (pintype "passive"))
      (node (ref "R20") (pin "1") (pinfunction "2_1") (pintype "passive"))
    )
    (net (code "43") (name "Net-(R21-2)") (class "Default")
      (node (ref "R21") (pin "1") (pinfunction "2_1") (pintype "passive"))
      (node (ref "R22") (pin "1") (pinfunction "2_1") (pintype "passive"))
      (node (ref "U7") (pin "4") (pinfunction "4_4") (pintype "passive"))
    )
    (net (code "44") (name "Net-(R21-3)") (class "Default")
      (node (ref "R21") (pin "2") (pinfunction "3_2") (pintype "passive"))
      (node (ref "U6") (pin "3") (pinfunction "G_3") (pintype "passive"))
    )
    (net (code "45") (name "Net-(R23-3)") (class "Default")
      (node (ref "JP3") (pin "1") (pinfunction "1_1") (pintype "passive"))
      (node (ref "R23") (pin "2") (pinfunction "3_2") (pintype "passive"))
    )
    (net (code "46") (name "Net-(R24-3)") (class "Default")
      (node (ref "JP3") (pin "3") (pinfunction "3_3") (pintype "passive"))
      (node (ref "R24") (pin "2") (pinfunction "3_2") (pintype "passive"))
    )
    (net (code "47") (name "Net-(R25-3)") (class "Default")
      (node (ref "JP3") (pin "4") (pinfunction "4_4") (pintype "passive"))
      (node (ref "R25") (pin "2") (pinfunction "3_2") (pintype "passive"))
    )
    (net (code "48") (name "unconnected-(J4-Pad3)") (class "Default")
      (node (ref "J4") (pin "3") (pinfunction "3_3") (pintype "passive+no_connect"))
    )
    (net (code "49") (name "unconnected-(U1-5A-Pad11)") (class "Default")
      (node (ref "U1") (pin "11") (pinfunction "5A_11") (pintype "passive"))
    )
    (net (code "50") (name "unconnected-(U1-5Y-Pad10)") (class "Default")
      (node (ref "U1") (pin "10") (pinfunction "5Y_10") (pintype "passive"))
    )
    (net (code "51") (name "unconnected-(U1-6A-Pad13)") (class "Default")
      (node (ref "U1") (pin "13") (pinfunction "6A_13") (pintype "passive"))
    )
    (net (code "52") (name "unconnected-(U1-6Y-Pad12)") (class "Default")
      (node (ref "U1") (pin "12") (pinfunction "6Y_12") (pintype "passive"))
    )
    (net (code "53") (name "unconnected-(U4-~{CO}-Pad7)") (class "Default")
      (node (ref "U4") (pin "7") (pinfunction "~{CO}_7") (pintype "passive"))
    )
    (net (code "54") (name "unconnected-(U5-RST-Pad4)") (class "Default")
      (node (ref "U5") (pin "4") (pinfunction "RST_4") (pintype "passive+no_connect"))
    )
    (net (code "55") (name "unconnected-(U7-NC-Pad3)") (class "Default")
      (node (ref "U7") (pin "3") (pinfunction "NC_3") (pintype "passive"))
    )
    (net (code "56") (name "unconnected-(U7-Pad6)") (class "Default")
      (node (ref "U7") (pin "6") (pinfunction "6_6") (pintype "passive+no_connect"))
    )
  )
)
